# CerberusZero_V1.net
KiCad netlist of a schematic drawn in EasyEDA Pro
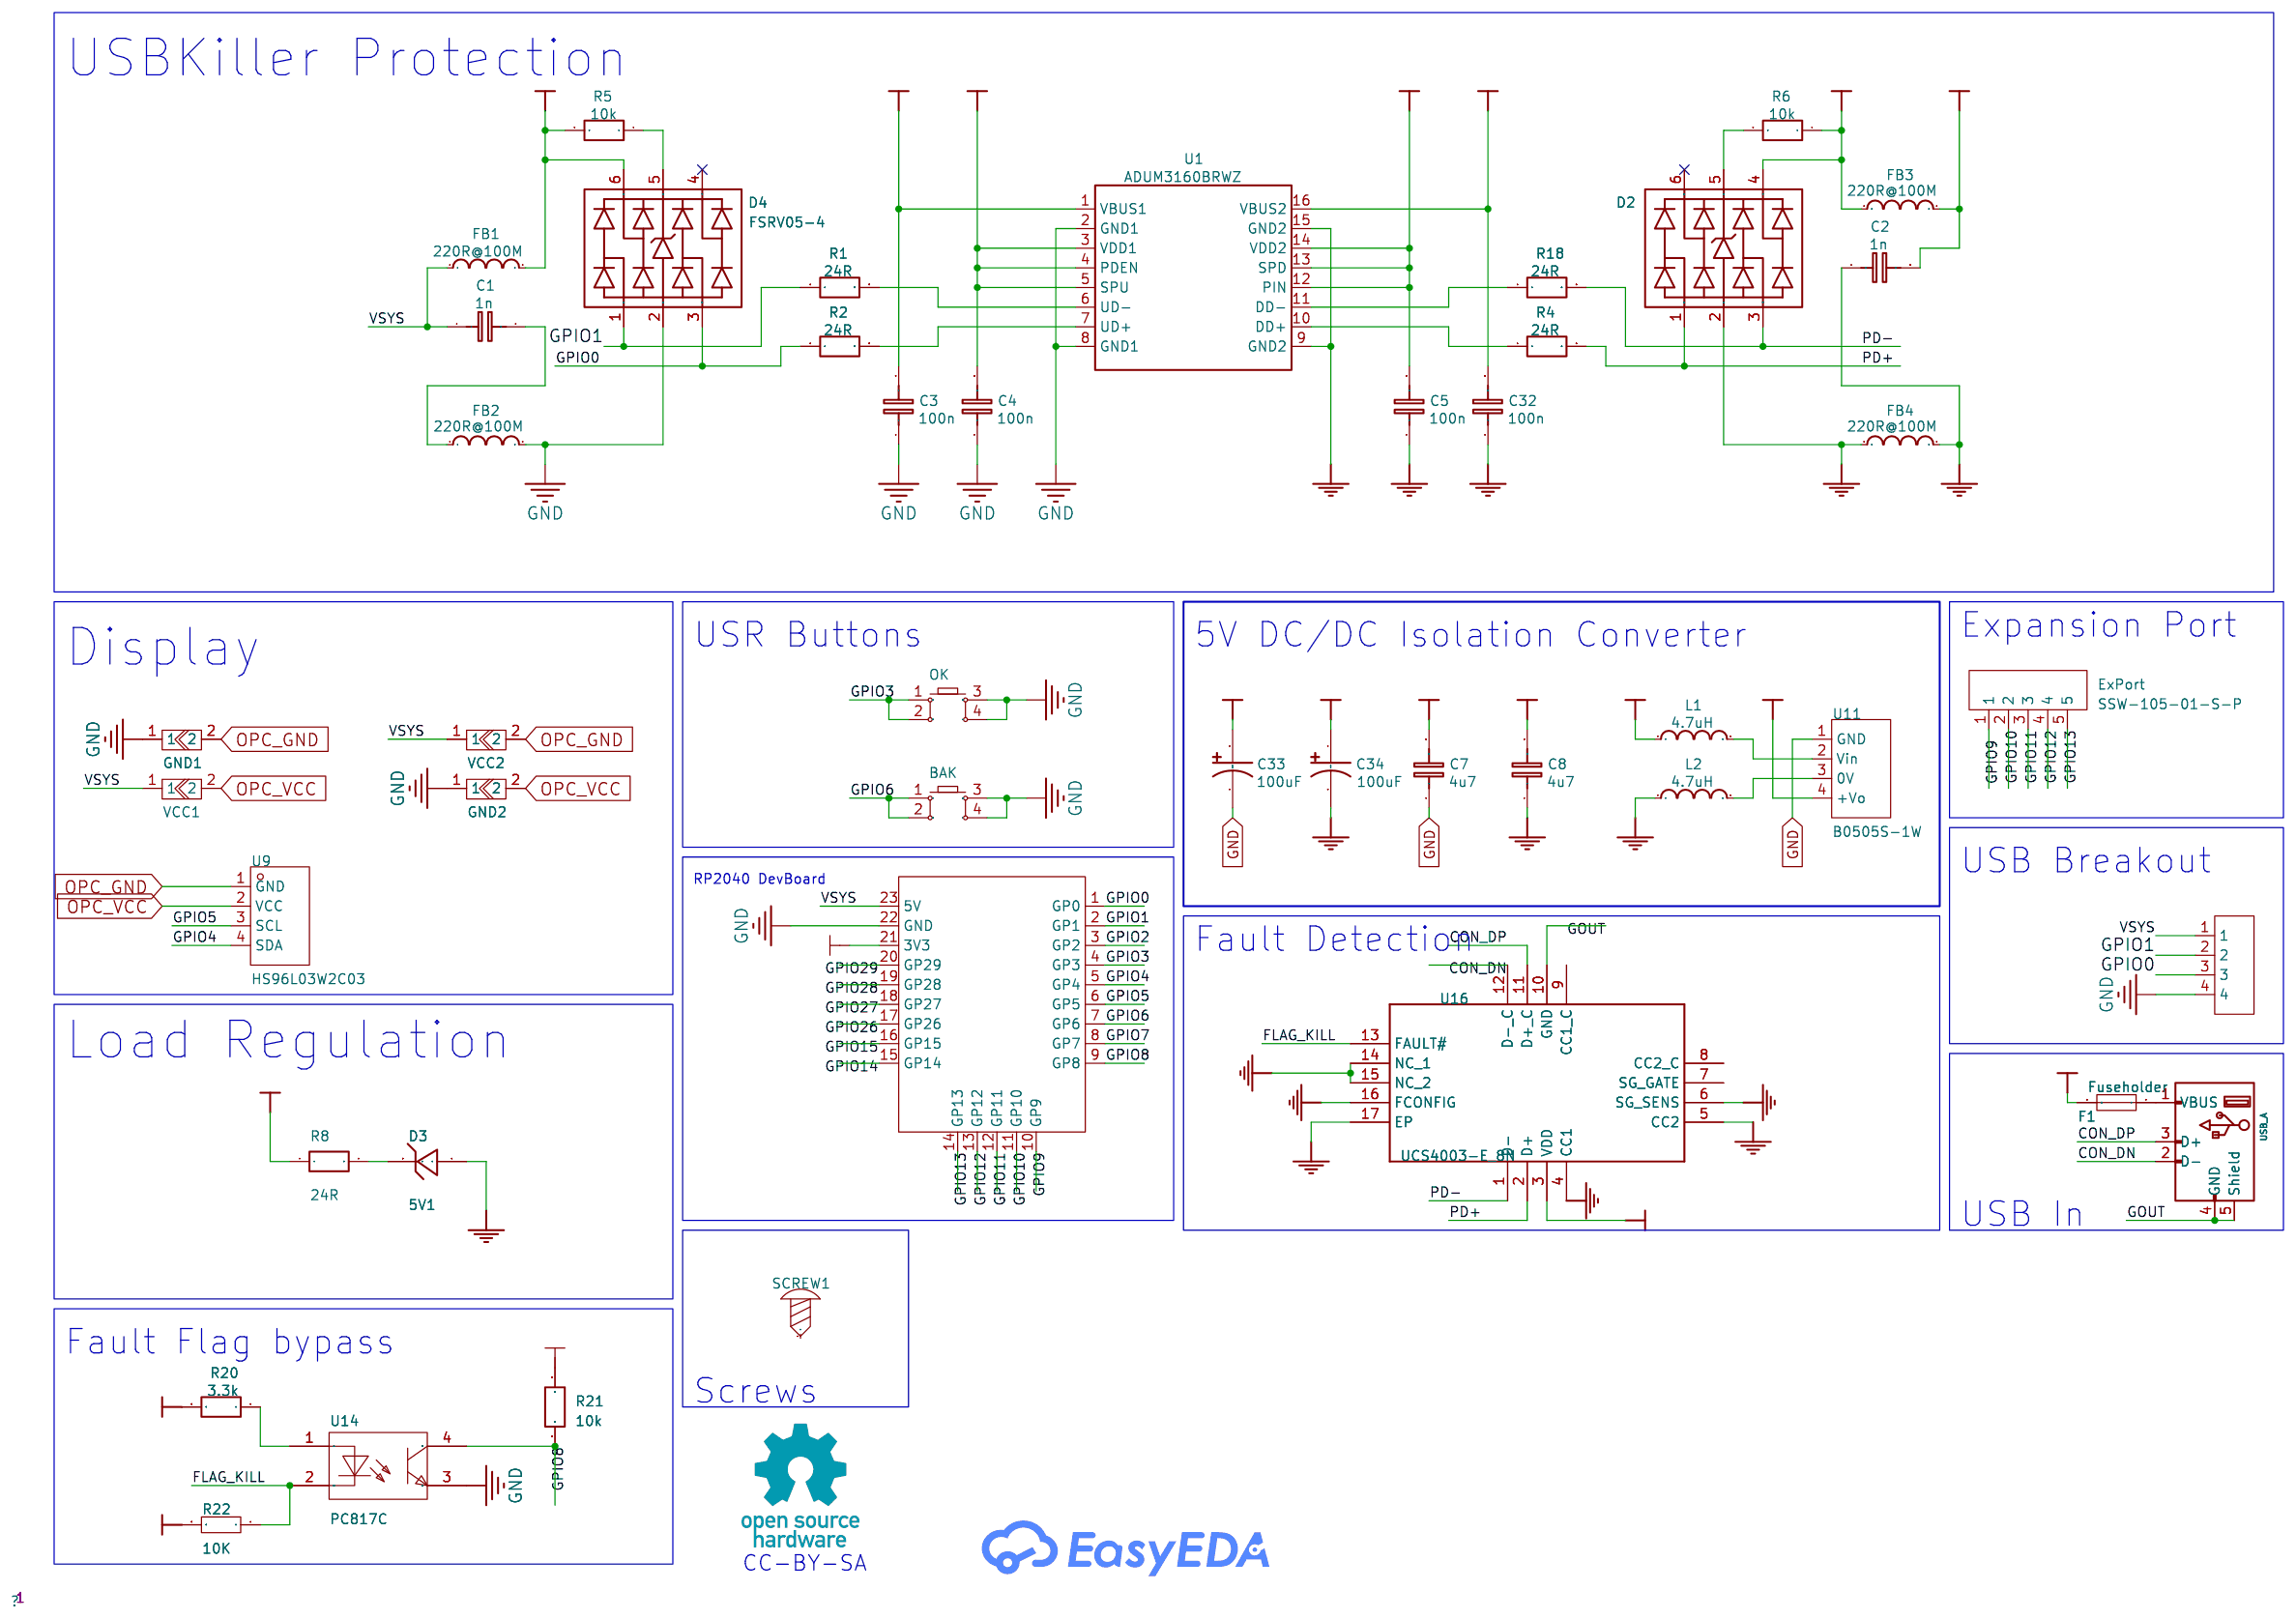
[diagram p0: schematic sheet]

(export (version "E")
  (design (tool "Eeschema 10.0.6"))
  (components
    (comp (ref "BAK")
      (value "PTS815SJK250SMTRLFS")
      (footprint "easyedapro:SW-SMD_4P-L4.2-W3.3-P2.15-LS5.1")
      (description "操作寿命10万次，使用温度-20°C 至 70°C,尺寸4.20mmx3.20mmx2.50mm，操作力度2.5N")
      (fields (field (name "Manufacturer") "C&K"))
      (libsource (lib "easyedapro") (part "PTS815SJK250SMTRLFS"))
    )
    (comp (ref "C1")
      (value "1n")
      (fields (field (name "Manufacturer Part") "CL10B102KB8NNNC") (field (name "Manufacturer") "SAMSUNG"))
      (libsource (lib "easyedapro") (part "1n"))
    )
    (comp (ref "C2")
      (value "1n")
      (fields (field (name "Manufacturer Part") "CL10B102KB8NNNC") (field (name "Manufacturer") "SAMSUNG"))
      (libsource (lib "easyedapro") (part "1n"))
    )
    (comp (ref "C3")
      (value "100n")
      (fields (field (name "Manufacturer Part") "CC0603KRX7R9BB104") (field (name "Manufacturer") "YAGEO"))
      (libsource (lib "easyedapro") (part "100n"))
    )
    (comp (ref "C4")
      (value "100n")
      (fields (field (name "Manufacturer Part") "CC0603KRX7R9BB104") (field (name "Manufacturer") "YAGEO"))
      (libsource (lib "easyedapro") (part "100n"))
    )
    (comp (ref "C5")
      (value "100n")
      (fields (field (name "Manufacturer Part") "CC0603KRX7R9BB104") (field (name "Manufacturer") "YAGEO"))
      (libsource (lib "easyedapro") (part "100n"))
    )
    (comp (ref "C7")
      (value "4u7")
      (fields (field (name "Manufacturer Part") "CL10A475KO8NNNC") (field (name "Manufacturer") "SAMSUNG"))
      (libsource (lib "easyedapro") (part "4u7"))
    )
    (comp (ref "C8")
      (value "4u7")
      (fields (field (name "Manufacturer Part") "CL10A475KO8NNNC") (field (name "Manufacturer") "SAMSUNG"))
      (libsource (lib "easyedapro") (part "4u7"))
    )
    (comp (ref "C32")
      (value "100n")
      (fields (field (name "Manufacturer Part") "CC0603KRX7R9BB104") (field (name "Manufacturer") "YAGEO"))
      (libsource (lib "easyedapro") (part "100n"))
    )
    (comp (ref "C33")
      (value "100uF")
      (fields
        (field (name "Manufacturer Part") "TAJC107M016RNJ")
        (field (name "Manufacturer") "AVX")
        (field (name "Contributor") "LCSC")
      )
      (libsource (lib "easyedapro") (part "100uF"))
    )
    (comp (ref "C34")
      (value "100uF")
      (fields
        (field (name "Manufacturer Part") "TAJC107M016RNJ")
        (field (name "Manufacturer") "AVX")
        (field (name "Contributor") "LCSC")
      )
      (libsource (lib "easyedapro") (part "100uF"))
    )
    (comp (ref "D2")
      (value "FSRV05-4")
      (fields (field (name "Manufacturer") "FUXINSEMI"))
      (libsource (lib "easyedapro") (part "FSRV05-4"))
    )
    (comp (ref "D3")
      (value "5V1")
      (fields
        (field (name "Manufacturer Part") "MM1Z5V1")
        (field (name "Manufacturer") "SEMTECH")
        (field (name "Contributor") "LCSC")
      )
      (libsource (lib "easyedapro") (part "5V1"))
    )
    (comp (ref "D4")
      (value "FSRV05-4")
      (fields (field (name "Manufacturer") "FUXINSEMI") (field (name "Contributor") "Stefan Wagner"))
      (libsource (lib "easyedapro") (part "FSRV05-4"))
    )
    (comp (ref "ExPort")
      (value "SSW-105-01-S-P")
      (footprint "easyedapro:HDR-TH_5P-P2.54_SSW-105-01-S-P")
      (fields (field (name "Manufacturer") "SAMTEC"))
      (libsource (lib "easyedapro") (part "SSW-105-01-S-P"))
    )
    (comp (ref "F1")
      (value "Fuseholder")
      (footprint "easyedapro:FUSE-SMD_L9.7-W5.0")
      (libsource (lib "easyedapro") (part "1808 SMD FUSEHOLDER"))
    )
    (comp (ref "FB1")
      (value "220Ω")
      (footprint "easyedapro:L0603")
      (fields (field (name "Manufacturer Part") "UPZ1608E221-2R0TF") (field (name "Manufacturer") "Sunlord"))
      (libsource (lib "easyedapro") (part "220R@100M"))
    )
    (comp (ref "FB2")
      (value "220Ω")
      (footprint "easyedapro:L0603")
      (fields (field (name "Manufacturer Part") "UPZ1608E221-2R0TF") (field (name "Manufacturer") "Sunlord"))
      (libsource (lib "easyedapro") (part "220R@100M"))
    )
    (comp (ref "FB3")
      (value "220Ω")
      (footprint "easyedapro:L0603")
      (fields (field (name "Manufacturer Part") "UPZ1608E221-2R0TF") (field (name "Manufacturer") "Sunlord"))
      (libsource (lib "easyedapro") (part "220R@100M"))
    )
    (comp (ref "FB4")
      (value "220Ω")
      (footprint "easyedapro:L0603")
      (fields (field (name "Manufacturer Part") "UPZ1608E221-2R0TF") (field (name "Manufacturer") "Sunlord"))
      (libsource (lib "easyedapro") (part "220R@100M"))
    )
    (comp (ref "GND1")
      (value "~")
      (footprint "easyedapro:Solder Jumper 0402")
      (description "Solder Jumper for 0402 components")
      (libsource (lib "easyedapro") (part "Solder Jumper"))
    )
    (comp (ref "GND2")
      (value "~")
      (footprint "easyedapro:Solder Jumper 0402")
      (description "Solder Jumper for 0402 components")
      (libsource (lib "easyedapro") (part "Solder Jumper"))
    )
    (comp (ref "L1")
      (value "220Ω")
      (footprint "easyedapro:L0603")
      (fields
        (field (name "Manufacturer Part") "CPY160808T-4R7M-NP")
        (field (name "Manufacturer") "Chilisin Elec")
      )
      (libsource (lib "easyedapro") (part "4.7uH"))
    )
    (comp (ref "L2")
      (value "220Ω")
      (footprint "easyedapro:L0603")
      (fields
        (field (name "Manufacturer Part") "CPY160808T-4R7M-NP")
        (field (name "Manufacturer") "Chilisin Elec")
      )
      (libsource (lib "easyedapro") (part "4.7uH"))
    )
    (comp (ref "OK")
      (value "PTS815SJK250SMTRLFS")
      (footprint "easyedapro:SW-SMD_4P-L4.2-W3.3-P2.15-LS5.1")
      (description "操作寿命10万次，使用温度-20°C 至 70°C,尺寸4.20mmx3.20mmx2.50mm，操作力度2.5N")
      (fields (field (name "Manufacturer") "C&K"))
      (libsource (lib "easyedapro") (part "PTS815SJK250SMTRLFS"))
    )
    (comp (ref "R1")
      (value "24R")
      (fields (field (name "Manufacturer Part") "0603WAF240JT5E") (field (name "Manufacturer") "UniOhm"))
      (libsource (lib "easyedapro") (part "24R"))
    )
    (comp (ref "R2")
      (value "24R")
      (fields (field (name "Manufacturer Part") "0603WAF240JT5E") (field (name "Manufacturer") "UniOhm"))
      (libsource (lib "easyedapro") (part "24R"))
    )
    (comp (ref "R4")
      (value "24R")
      (fields (field (name "Manufacturer Part") "0603WAF240JT5E") (field (name "Manufacturer") "UniOhm"))
      (libsource (lib "easyedapro") (part "24R"))
    )
    (comp (ref "R5")
      (value "10k")
      (fields (field (name "Manufacturer Part") "0603WAF1002T5E") (field (name "Manufacturer") "UniOhm"))
      (libsource (lib "easyedapro") (part "10k"))
    )
    (comp (ref "R6")
      (value "10k")
      (fields (field (name "Manufacturer Part") "0603WAF1002T5E") (field (name "Manufacturer") "UniOhm"))
      (libsource (lib "easyedapro") (part "10k"))
    )
    (comp (ref "R8")
      (value "24R")
      (fields (field (name "Manufacturer Part") "0603WAF240JT5E") (field (name "Manufacturer") "UniOhm"))
      (libsource (lib "easyedapro") (part "24R"))
    )
    (comp (ref "R18")
      (value "24R")
      (fields (field (name "Manufacturer Part") "0603WAF240JT5E") (field (name "Manufacturer") "UniOhm"))
      (libsource (lib "easyedapro") (part "24R"))
    )
    (comp (ref "R20")
      (value "3.3k")
      (fields (field (name "Manufacturer Part") "0603WAF1002T5E") (field (name "Manufacturer") "UniOhm"))
      (libsource (lib "easyedapro") (part "10k"))
    )
    (comp (ref "R21")
      (value "10k")
      (fields (field (name "Manufacturer Part") "0603WAF1002T5E") (field (name "Manufacturer") "UniOhm"))
      (libsource (lib "easyedapro") (part "10k"))
    )
    (comp (ref "R22")
      (value "10K")
      (footprint "easyedapro:R0603")
      (libsource (lib "easyedapro") (part "Res"))
    )
    (comp (ref "SCREW1")
      (value "~")
      (footprint "easyedapro:Screw-Hole-M3")
      (libsource (lib "easyedapro") (part "Screw-Hole"))
    )
    (comp (ref "U1")
      (value "ADUM3160BRWZ")
      (footprint "easyedapro:SOIC-16_L10.3-W7.5-P1.27-LS10.3-TL")
      (fields (field (name "Manufacturer") "ADI") (field (name "Contributor") "LCSC"))
      (libsource (lib "easyedapro") (part "ADUM3160BRWZ"))
    )
    (comp (ref "U9")
      (value "HS96L03W2C03")
      (footprint "easyedapro:OLED-TH_L27.8-W27.2-P2.54_C9900033791")
      (fields (field (name "Manufacturer") "HS(汉昇)"))
      (libsource (lib "easyedapro") (part "HS96L03W2C03"))
    )
    (comp (ref "U11")
      (value "B0505S-1W")
      (footprint "easyedapro:PWRM-TH_BXXXXS-1W")
      (fields (field (name "Manufacturer") "TESL*A(清远特斯拉)"))
      (libsource (lib "easyedapro") (part "B0505S-1W_C2880020"))
    )
    (comp (ref "U14")
      (value "PC817C")
      (footprint "easyedapro:DIP-4_L4.6-W6.5-P2.54-LS7.6-BL")
      (fields (field (name "Manufacturer") "KTP(科泰普)"))
      (libsource (lib "easyedapro") (part "PC817C_C20612449"))
    )
    (comp (ref "U15")
      (value "RP2040-Zero")
      (footprint "easyedapro:COMM-SMD_RP2040-ZERO")
      (fields (field (name "Manufacturer") "Waveshare(微雪电子)"))
      (libsource (lib "easyedapro") (part "RP2040-ZERO"))
    )
    (comp (ref "U16")
      (value "UCS4003-E_8N")
      (footprint "easyedapro:QFN50P300X300X100-17N")
      (description "USB Interface IC USB Type-C Port Protector")
      (libsource (lib "easyedapro") (part "UCS4003-E_8N"))
    )
    (comp (ref "USB_B")
      (value "HX PH254-01-04-Z-L11.5 straight pin header")
      (footprint "easyedapro:HDR-TH_4P-HX-PH254-01-04-Z-L11.5")
      (fields (field (name "Manufacturer") "hanxia(韩下)"))
      (libsource (lib "easyedapro") (part "HX PH254-01-04-Z-L11.5 STRAIGHT PIN HEADER"))
    )
    (comp (ref "USB_IN1")
      (value "USB_A")
      (footprint "easyedapro:usbCondom:875832010BLF")
      (libsource (lib "easyedapro") (part "Connector_USB_A"))
    )
    (comp (ref "VCC1")
      (value "~")
      (footprint "easyedapro:Solder Jumper 0402")
      (description "Solder Jumper for 0402 components")
      (libsource (lib "easyedapro") (part "Solder Jumper"))
    )
    (comp (ref "VCC2")
      (value "~")
      (footprint "easyedapro:Solder Jumper 0402")
      (description "Solder Jumper for 0402 components")
      (libsource (lib "easyedapro") (part "Solder Jumper"))
    )
  )
  (nets
    (net (code "1") (name "/CON_DN") (class "Default")
      (node (ref "U16") (pin "12") (pinfunction "D-_C_12") (pintype "bidirectional"))
      (node (ref "USB_IN1") (pin "2") (pinfunction "D-_2") (pintype "bidirectional"))
    )
    (net (code "2") (name "/CON_DP") (class "Default")
      (node (ref "U16") (pin "11") (pinfunction "D+_C_11") (pintype "bidirectional"))
      (node (ref "USB_IN1") (pin "3") (pinfunction "D+_3") (pintype "bidirectional"))
    )
    (net (code "3") (name "/FLAG_KILL") (class "Default")
      (node (ref "R22") (pin "1") (pinfunction "1_1") (pintype "input"))
      (node (ref "U14") (pin "2") (pinfunction "CAT_2") (pintype "unspecified"))
      (node (ref "U16") (pin "13") (pinfunction "FAULT#_13") (pintype "bidirectional"))
    )
    (net (code "4") (name "/GPIO0") (class "Default")
      (node (ref "D4") (pin "3") (pinfunction "3_3") (pintype "unspecified"))
      (node (ref "R2") (pin "1") (pinfunction "1_1") (pintype "unspecified"))
      (node (ref "U15") (pin "1") (pinfunction "GP0_1") (pintype "unspecified"))
      (node (ref "USB_B") (pin "3") (pinfunction "3_3") (pintype "unspecified"))
    )
    (net (code "5") (name "/GPIO1") (class "Default")
      (node (ref "D4") (pin "1") (pinfunction "1_1") (pintype "unspecified"))
      (node (ref "R1") (pin "1") (pinfunction "1_1") (pintype "unspecified"))
      (node (ref "U15") (pin "2") (pinfunction "GP1_2") (pintype "unspecified"))
      (node (ref "USB_B") (pin "2") (pinfunction "2_2") (pintype "unspecified"))
    )
    (net (code "6") (name "/GPIO2") (class "Default")
      (node (ref "U15") (pin "3") (pinfunction "GP2_3") (pintype "unspecified"))
    )
    (net (code "7") (name "/GPIO3") (class "Default")
      (node (ref "OK") (pin "1") (pinfunction "1_1") (pintype "input"))
      (node (ref "OK") (pin "2") (pinfunction "2_2") (pintype "input"))
      (node (ref "U15") (pin "4") (pinfunction "GP3_4") (pintype "unspecified"))
    )
    (net (code "8") (name "/GPIO4") (class "Default")
      (node (ref "U15") (pin "5") (pinfunction "GP4_5") (pintype "unspecified"))
      (node (ref "U9") (pin "4") (pinfunction "SDA_4") (pintype "unspecified"))
    )
    (net (code "9") (name "/GPIO5") (class "Default")
      (node (ref "U15") (pin "6") (pinfunction "GP5_6") (pintype "unspecified"))
      (node (ref "U9") (pin "3") (pinfunction "SCL_3") (pintype "unspecified"))
    )
    (net (code "10") (name "/GPIO6") (class "Default")
      (node (ref "BAK") (pin "1") (pinfunction "1_1") (pintype "input"))
      (node (ref "BAK") (pin "2") (pinfunction "2_2") (pintype "input"))
      (node (ref "U15") (pin "7") (pinfunction "GP6_7") (pintype "unspecified"))
    )
    (net (code "11") (name "/GPIO7") (class "Default")
      (node (ref "U15") (pin "8") (pinfunction "GP7_8") (pintype "unspecified"))
    )
    (net (code "12") (name "/GPIO8") (class "Default")
      (node (ref "R21") (pin "1") (pinfunction "1_1") (pintype "unspecified"))
      (node (ref "U14") (pin "4") (pinfunction "COL_4") (pintype "unspecified"))
      (node (ref "U15") (pin "9") (pinfunction "GP8_9") (pintype "unspecified"))
    )
    (net (code "13") (name "/GPIO9") (class "Default")
      (node (ref "ExPort") (pin "1") (pinfunction "1_1") (pintype "unspecified"))
      (node (ref "U15") (pin "10") (pinfunction "GP9_10") (pintype "unspecified"))
    )
    (net (code "14") (name "/GPIO10") (class "Default")
      (node (ref "ExPort") (pin "2") (pinfunction "2_2") (pintype "unspecified"))
      (node (ref "U15") (pin "11") (pinfunction "GP10_11") (pintype "unspecified"))
    )
    (net (code "15") (name "/GPIO11") (class "Default")
      (node (ref "ExPort") (pin "3") (pinfunction "3_3") (pintype "unspecified"))
      (node (ref "U15") (pin "12") (pinfunction "GP11_12") (pintype "unspecified"))
    )
    (net (code "16") (name "/GPIO12") (class "Default")
      (node (ref "ExPort") (pin "4") (pinfunction "4_4") (pintype "unspecified"))
      (node (ref "U15") (pin "13") (pinfunction "GP12_13") (pintype "unspecified"))
    )
    (net (code "17") (name "/GPIO13") (class "Default")
      (node (ref "ExPort") (pin "5") (pinfunction "5_5") (pintype "unspecified"))
      (node (ref "U15") (pin "14") (pinfunction "GP13_14") (pintype "unspecified"))
    )
    (net (code "18") (name "/GPIO14") (class "Default")
      (node (ref "U15") (pin "15") (pinfunction "GP14_15") (pintype "unspecified"))
    )
    (net (code "19") (name "/GPIO15") (class "Default")
      (node (ref "U15") (pin "16") (pinfunction "GP15_16") (pintype "unspecified"))
    )
    (net (code "20") (name "/GPIO26") (class "Default")
      (node (ref "U15") (pin "17") (pinfunction "GP26_17") (pintype "unspecified"))
    )
    (net (code "21") (name "/GPIO27") (class "Default")
      (node (ref "U15") (pin "18") (pinfunction "GP27_18") (pintype "unspecified"))
    )
    (net (code "22") (name "/GPIO28") (class "Default")
      (node (ref "U15") (pin "19") (pinfunction "GP28_19") (pintype "unspecified"))
    )
    (net (code "23") (name "/GPIO29") (class "Default")
      (node (ref "U15") (pin "20") (pinfunction "GP29_20") (pintype "unspecified"))
    )
    (net (code "24") (name "/PD+") (class "Default")
      (node (ref "D2") (pin "1") (pinfunction "1_1") (pintype "unspecified"))
      (node (ref "R4") (pin "2") (pinfunction "2_2") (pintype "unspecified"))
      (node (ref "U16") (pin "2") (pinfunction "D+_2") (pintype "bidirectional"))
    )
    (net (code "25") (name "/PD-") (class "Default")
      (node (ref "D2") (pin "3") (pinfunction "3_3") (pintype "unspecified"))
      (node (ref "R18") (pin "2") (pinfunction "2_2") (pintype "unspecified"))
      (node (ref "U16") (pin "1") (pinfunction "D-_1") (pintype "bidirectional"))
    )
    (net (code "26") (name "/VSYS") (class "Default")
      (node (ref "C1") (pin "1") (pinfunction "1_1") (pintype "unspecified"))
      (node (ref "FB1") (pin "1") (pinfunction "1_1") (pintype "unspecified"))
      (node (ref "U15") (pin "23") (pinfunction "5V_23") (pintype "unspecified"))
      (node (ref "USB_B") (pin "1") (pinfunction "1_1") (pintype "unspecified"))
      (node (ref "VCC1") (pin "1") (pinfunction "1_1") (pintype "input"))
      (node (ref "VCC2") (pin "1") (pinfunction "1_1") (pintype "input"))
    )
    (net (code "27") (name "3V3") (class "Default")
      (node (ref "R21") (pin "2") (pinfunction "2_2") (pintype "unspecified"))
      (node (ref "U15") (pin "21") (pinfunction "3V3_21") (pintype "unspecified"))
    )
    (net (code "28") (name "GND") (class "Default")
      (node (ref "BAK") (pin "3") (pinfunction "3_3") (pintype "input"))
      (node (ref "BAK") (pin "4") (pinfunction "4_4") (pintype "input"))
      (node (ref "C3") (pin "1") (pinfunction "1_1") (pintype "unspecified"))
      (node (ref "C33") (pin "2") (pinfunction "2_2") (pintype "unspecified"))
      (node (ref "C4") (pin "1") (pinfunction "1_1") (pintype "unspecified"))
      (node (ref "C7") (pin "1") (pinfunction "1_1") (pintype "unspecified"))
      (node (ref "D4") (pin "2") (pinfunction "2_2") (pintype "unspecified"))
      (node (ref "FB2") (pin "2") (pinfunction "2_2") (pintype "unspecified"))
      (node (ref "GND1") (pin "1") (pinfunction "1_1") (pintype "input"))
      (node (ref "GND2") (pin "1") (pinfunction "1_1") (pintype "input"))
      (node (ref "OK") (pin "3") (pinfunction "3_3") (pintype "input"))
      (node (ref "OK") (pin "4") (pinfunction "4_4") (pintype "input"))
      (node (ref "U1") (pin "2") (pinfunction "GND1_2") (pintype "unspecified"))
      (node (ref "U1") (pin "8") (pinfunction "GND1_8") (pintype "unspecified"))
      (node (ref "U11") (pin "1") (pinfunction "GND_1") (pintype "unspecified"))
      (node (ref "U14") (pin "3") (pinfunction "EM_3") (pintype "unspecified"))
      (node (ref "U15") (pin "22") (pinfunction "GND_22") (pintype "unspecified"))
      (node (ref "USB_B") (pin "4") (pinfunction "4_4") (pintype "unspecified"))
    )
    (net (code "29") (name "GND2") (class "Default")
      (node (ref "C32") (pin "1") (pinfunction "1_1") (pintype "unspecified"))
      (node (ref "C34") (pin "2") (pinfunction "2_2") (pintype "unspecified"))
      (node (ref "C5") (pin "1") (pinfunction "1_1") (pintype "unspecified"))
      (node (ref "C8") (pin "1") (pinfunction "1_1") (pintype "unspecified"))
      (node (ref "D2") (pin "2") (pinfunction "2_2") (pintype "unspecified"))
      (node (ref "FB4") (pin "1") (pinfunction "1_1") (pintype "unspecified"))
      (node (ref "L2") (pin "1") (pinfunction "1_1") (pintype "unspecified"))
      (node (ref "U1") (pin "15") (pinfunction "GND2_15") (pintype "unspecified"))
      (node (ref "U1") (pin "9") (pinfunction "GND2_9") (pintype "unspecified"))
      (node (ref "U16") (pin "14") (pinfunction "NC_1_14") (pintype "bidirectional"))
      (node (ref "U16") (pin "15") (pinfunction "NC_2_15") (pintype "bidirectional"))
      (node (ref "U16") (pin "16") (pinfunction "FCONFIG_16") (pintype "bidirectional"))
      (node (ref "U16") (pin "17") (pinfunction "EP_17") (pintype "bidirectional"))
      (node (ref "U16") (pin "4") (pinfunction "CC1_4") (pintype "bidirectional"))
      (node (ref "U16") (pin "5") (pinfunction "CC2_5") (pintype "bidirectional"))
      (node (ref "U16") (pin "6") (pinfunction "SG_SENS_6") (pintype "bidirectional"))
    )
    (net (code "30") (name "GOUT") (class "Default")
      (node (ref "C2") (pin "1") (pinfunction "1_1") (pintype "unspecified"))
      (node (ref "D3") (pin "1") (pinfunction "A_1") (pintype "unspecified"))
      (node (ref "FB4") (pin "2") (pinfunction "2_2") (pintype "unspecified"))
      (node (ref "U16") (pin "10") (pinfunction "GND_10") (pintype "bidirectional"))
      (node (ref "USB_IN1") (pin "4") (pinfunction "GND_4") (pintype "unspecified"))
      (node (ref "USB_IN1") (pin "5") (pinfunction "Shield_5") (pintype "unspecified"))
    )
    (net (code "31") (name "Net-(C1-Pad2)") (class "Default")
      (node (ref "C1") (pin "2") (pinfunction "2_2") (pintype "unspecified"))
      (node (ref "FB2") (pin "1") (pinfunction "1_1") (pintype "unspecified"))
    )
    (net (code "32") (name "Net-(D2-Pad5)") (class "Default")
      (node (ref "D2") (pin "5") (pinfunction "5_5") (pintype "unspecified"))
      (node (ref "R6") (pin "2") (pinfunction "2_2") (pintype "unspecified"))
    )
    (net (code "33") (name "Net-(D3-K)") (class "Default")
      (node (ref "D3") (pin "2") (pinfunction "K_2") (pintype "unspecified"))
      (node (ref "R8") (pin "2") (pinfunction "2_2") (pintype "unspecified"))
    )
    (net (code "34") (name "Net-(D4-Pad5)") (class "Default")
      (node (ref "D4") (pin "5") (pinfunction "5_5") (pintype "unspecified"))
      (node (ref "R5") (pin "1") (pinfunction "1_1") (pintype "unspecified"))
    )
    (net (code "35") (name "Net-(U1-DD+)") (class "Default")
      (node (ref "R4") (pin "1") (pinfunction "1_1") (pintype "unspecified"))
      (node (ref "U1") (pin "10") (pinfunction "DD+_10") (pintype "unspecified"))
    )
    (net (code "36") (name "Net-(U1-DD-)") (class "Default")
      (node (ref "R18") (pin "1") (pinfunction "1_1") (pintype "unspecified"))
      (node (ref "U1") (pin "11") (pinfunction "DD-_11") (pintype "unspecified"))
    )
    (net (code "37") (name "Net-(U1-UD+)") (class "Default")
      (node (ref "R2") (pin "2") (pinfunction "2_2") (pintype "unspecified"))
      (node (ref "U1") (pin "7") (pinfunction "UD+_7") (pintype "unspecified"))
    )
    (net (code "38") (name "Net-(U1-UD-)") (class "Default")
      (node (ref "R1") (pin "2") (pinfunction "2_2") (pintype "unspecified"))
      (node (ref "U1") (pin "6") (pinfunction "UD-_6") (pintype "unspecified"))
    )
    (net (code "39") (name "Net-(U11-0V)") (class "Default")
      (node (ref "L2") (pin "2") (pinfunction "2_2") (pintype "unspecified"))
      (node (ref "U11") (pin "3") (pinfunction "0V_3") (pintype "unspecified"))
    )
    (net (code "40") (name "Net-(U11-Vin)") (class "Default")
      (node (ref "L1") (pin "2") (pinfunction "2_2") (pintype "unspecified"))
      (node (ref "U11") (pin "2") (pinfunction "Vin_2") (pintype "unspecified"))
    )
    (net (code "41") (name "Net-(U14-AN)") (class "Default")
      (node (ref "R20") (pin "1") (pinfunction "1_1") (pintype "unspecified"))
      (node (ref "U14") (pin "1") (pinfunction "AN_1") (pintype "unspecified"))
    )
    (net (code "42") (name "Net-(USB_IN1-VBUS)") (class "Default")
      (node (ref "F1") (pin "1") (pinfunction "1_1") (pintype "unspecified"))
      (node (ref "USB_IN1") (pin "1") (pinfunction "VBUS_1") (pintype "unspecified"))
    )
    (net (code "43") (name "OPC_GND") (class "Default")
      (node (ref "GND1") (pin "2") (pinfunction "2_2") (pintype "input"))
      (node (ref "U9") (pin "1") (pinfunction "GND_1") (pintype "unspecified"))
      (node (ref "VCC2") (pin "2") (pinfunction "2_2") (pintype "input"))
    )
    (net (code "44") (name "OPC_VCC") (class "Default")
      (node (ref "GND2") (pin "2") (pinfunction "2_2") (pintype "input"))
      (node (ref "U9") (pin "2") (pinfunction "VCC_2") (pintype "unspecified"))
      (node (ref "VCC1") (pin "2") (pinfunction "2_2") (pintype "input"))
    )
    (net (code "45") (name "VBUS1") (class "Default")
      (node (ref "C3") (pin "2") (pinfunction "2_2") (pintype "unspecified"))
      (node (ref "C33") (pin "1") (pinfunction "1_1") (pintype "unspecified"))
      (node (ref "C7") (pin "2") (pinfunction "2_2") (pintype "unspecified"))
      (node (ref "D4") (pin "6") (pinfunction "6_6") (pintype "unspecified"))
      (node (ref "FB1") (pin "2") (pinfunction "2_2") (pintype "unspecified"))
      (node (ref "L1") (pin "1") (pinfunction "1_1") (pintype "unspecified"))
      (node (ref "R5") (pin "2") (pinfunction "2_2") (pintype "unspecified"))
      (node (ref "U1") (pin "1") (pinfunction "VBUS1_1") (pintype "unspecified"))
    )
    (net (code "46") (name "VBUS2") (class "Default")
      (node (ref "C32") (pin "2") (pinfunction "2_2") (pintype "unspecified"))
      (node (ref "C34") (pin "1") (pinfunction "1_1") (pintype "unspecified"))
      (node (ref "C8") (pin "2") (pinfunction "2_2") (pintype "unspecified"))
      (node (ref "D2") (pin "4") (pinfunction "4_4") (pintype "unspecified"))
      (node (ref "FB3") (pin "1") (pinfunction "1_1") (pintype "unspecified"))
      (node (ref "R20") (pin "2") (pinfunction "2_2") (pintype "unspecified"))
      (node (ref "R22") (pin "2") (pinfunction "2_2") (pintype "input"))
      (node (ref "R6") (pin "1") (pinfunction "1_1") (pintype "unspecified"))
      (node (ref "U1") (pin "16") (pinfunction "VBUS2_16") (pintype "unspecified"))
      (node (ref "U11") (pin "4") (pinfunction "+Vo_4") (pintype "unspecified"))
      (node (ref "U16") (pin "3") (pinfunction "VDD_3") (pintype "bidirectional"))
    )
    (net (code "47") (name "VDD1") (class "Default")
      (node (ref "C4") (pin "2") (pinfunction "2_2") (pintype "unspecified"))
      (node (ref "U1") (pin "3") (pinfunction "VDD1_3") (pintype "unspecified"))
      (node (ref "U1") (pin "4") (pinfunction "PDEN_4") (pintype "unspecified"))
      (node (ref "U1") (pin "5") (pinfunction "SPU_5") (pintype "unspecified"))
    )
    (net (code "48") (name "VDD2") (class "Default")
      (node (ref "C5") (pin "2") (pinfunction "2_2") (pintype "unspecified"))
      (node (ref "U1") (pin "12") (pinfunction "PIN_12") (pintype "unspecified"))
      (node (ref "U1") (pin "13") (pinfunction "SPD_13") (pintype "unspecified"))
      (node (ref "U1") (pin "14") (pinfunction "VDD2_14") (pintype "unspecified"))
    )
    (net (code "49") (name "VOUT") (class "Default")
      (node (ref "C2") (pin "2") (pinfunction "2_2") (pintype "unspecified"))
      (node (ref "F1") (pin "2") (pinfunction "2_2") (pintype "unspecified"))
      (node (ref "FB3") (pin "2") (pinfunction "2_2") (pintype "unspecified"))
      (node (ref "R8") (pin "1") (pinfunction "1_1") (pintype "unspecified"))
    )
    (net (code "50") (name "unconnected-(D2-Pad6)") (class "Default")
      (node (ref "D2") (pin "6") (pinfunction "6_6") (pintype "unspecified+no_connect"))
    )
    (net (code "51") (name "unconnected-(D4-Pad4)") (class "Default")
      (node (ref "D4") (pin "4") (pinfunction "4_4") (pintype "unspecified+no_connect"))
    )
    (net (code "52") (name "unconnected-(SCREW1-Pad1)") (class "Default")
      (node (ref "SCREW1") (pin "1") (pinfunction "1_1") (pintype "input"))
    )
    (net (code "53") (name "unconnected-(U16-CC1_C-Pad9)") (class "Default")
      (node (ref "U16") (pin "9") (pinfunction "CC1_C_9") (pintype "bidirectional"))
    )
    (net (code "54") (name "unconnected-(U16-CC2_C-Pad8)") (class "Default")
      (node (ref "U16") (pin "8") (pinfunction "CC2_C_8") (pintype "bidirectional"))
    )
    (net (code "55") (name "unconnected-(U16-SG_GATE-Pad7)") (class "Default")
      (node (ref "U16") (pin "7") (pinfunction "SG_GATE_7") (pintype "bidirectional"))
    )
  )
)
